# LM339.net
KiCad netlist of a schematic drawn in EAGLE
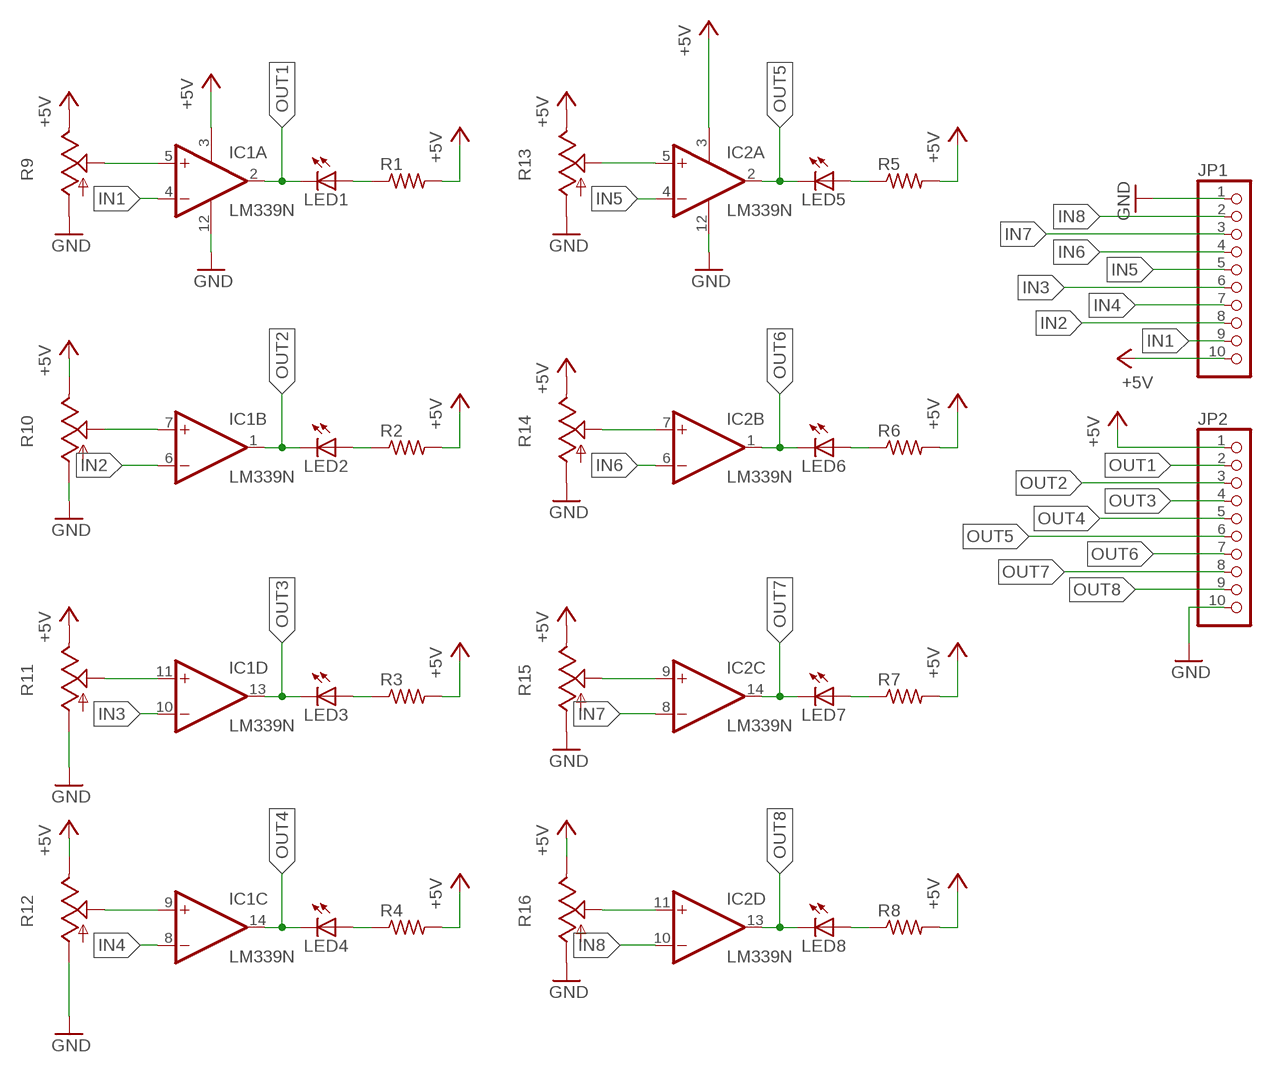
[diagram p0: schematic, sheet 1]

(export (version "E")
  (design (tool "Eeschema 10.0.6"))
  (components
    (comp (ref "IC1")
      (value "LM339N")
      (footprint "eagle-import:DIL14")
      (libsource (lib "eagle-import") (part "LM339N"))
    )
    (comp (ref "IC2")
      (value "LM339N")
      (footprint "eagle-import:DIL14")
      (libsource (lib "eagle-import") (part "LM339N"))
    )
    (comp (ref "JP1")
      (value "PINHD-1X10")
      (footprint "eagle-import:1X10")
      (libsource (lib "eagle-import") (part "PINHD-1X10"))
    )
    (comp (ref "JP2")
      (value "PINHD-1X10")
      (footprint "eagle-import:1X10")
      (libsource (lib "eagle-import") (part "PINHD-1X10"))
    )
    (comp (ref "LED1")
      (value "LED5MM")
      (footprint "eagle-import:LED5MM")
      (libsource (lib "eagle-import") (part "LED5MM"))
    )
    (comp (ref "LED2")
      (value "LED5MM")
      (footprint "eagle-import:LED5MM")
      (libsource (lib "eagle-import") (part "LED5MM"))
    )
    (comp (ref "LED3")
      (value "LED5MM")
      (footprint "eagle-import:LED5MM")
      (libsource (lib "eagle-import") (part "LED5MM"))
    )
    (comp (ref "LED4")
      (value "LED5MM")
      (footprint "eagle-import:LED5MM")
      (libsource (lib "eagle-import") (part "LED5MM"))
    )
    (comp (ref "LED5")
      (value "LED5MM")
      (footprint "eagle-import:LED5MM")
      (libsource (lib "eagle-import") (part "LED5MM"))
    )
    (comp (ref "LED6")
      (value "LED5MM")
      (footprint "eagle-import:LED5MM")
      (libsource (lib "eagle-import") (part "LED5MM"))
    )
    (comp (ref "LED7")
      (value "LED5MM")
      (footprint "eagle-import:LED5MM")
      (libsource (lib "eagle-import") (part "LED5MM"))
    )
    (comp (ref "LED8")
      (value "LED5MM")
      (footprint "eagle-import:LED5MM")
      (libsource (lib "eagle-import") (part "LED5MM"))
    )
    (comp (ref "R1")
      (value "R-US_0204/7")
      (footprint "eagle-import:0204_7")
      (libsource (lib "eagle-import") (part "R-US_0204/7"))
    )
    (comp (ref "R2")
      (value "R-US_0204/7")
      (footprint "eagle-import:0204_7")
      (libsource (lib "eagle-import") (part "R-US_0204/7"))
    )
    (comp (ref "R3")
      (value "R-US_0204/7")
      (footprint "eagle-import:0204_7")
      (libsource (lib "eagle-import") (part "R-US_0204/7"))
    )
    (comp (ref "R4")
      (value "R-US_0204/7")
      (footprint "eagle-import:0204_7")
      (libsource (lib "eagle-import") (part "R-US_0204/7"))
    )
    (comp (ref "R5")
      (value "R-US_0204/7")
      (footprint "eagle-import:0204_7")
      (libsource (lib "eagle-import") (part "R-US_0204/7"))
    )
    (comp (ref "R6")
      (value "R-US_0204/7")
      (footprint "eagle-import:0204_7")
      (libsource (lib "eagle-import") (part "R-US_0204/7"))
    )
    (comp (ref "R7")
      (value "R-US_0204/7")
      (footprint "eagle-import:0204_7")
      (libsource (lib "eagle-import") (part "R-US_0204/7"))
    )
    (comp (ref "R8")
      (value "R-US_0204/7")
      (footprint "eagle-import:0204_7")
      (libsource (lib "eagle-import") (part "R-US_0204/7"))
    )
    (comp (ref "R9")
      (value "TRIM_US-B25P")
      (footprint "eagle-import:B25P")
      (libsource (lib "eagle-import") (part "TRIM_US-B25P"))
    )
    (comp (ref "R10")
      (value "TRIM_US-B25P")
      (footprint "eagle-import:B25P")
      (libsource (lib "eagle-import") (part "TRIM_US-B25P"))
    )
    (comp (ref "R11")
      (value "TRIM_US-B25P")
      (footprint "eagle-import:B25P")
      (libsource (lib "eagle-import") (part "TRIM_US-B25P"))
    )
    (comp (ref "R12")
      (value "TRIM_US-B25P")
      (footprint "eagle-import:B25P")
      (libsource (lib "eagle-import") (part "TRIM_US-B25P"))
    )
    (comp (ref "R13")
      (value "TRIM_US-B25P")
      (footprint "eagle-import:B25P")
      (libsource (lib "eagle-import") (part "TRIM_US-B25P"))
    )
    (comp (ref "R14")
      (value "TRIM_US-B25P")
      (footprint "eagle-import:B25P")
      (libsource (lib "eagle-import") (part "TRIM_US-B25P"))
    )
    (comp (ref "R15")
      (value "TRIM_US-B25P")
      (footprint "eagle-import:B25P")
      (libsource (lib "eagle-import") (part "TRIM_US-B25P"))
    )
    (comp (ref "R16")
      (value "TRIM_US-B25P")
      (footprint "eagle-import:B25P")
      (libsource (lib "eagle-import") (part "TRIM_US-B25P"))
    )
  )
  (nets
    (net (code "1") (name "+5V") (class "Default")
      (node (ref "IC1") (pin "3") (pinfunction "V+_3") (pintype "power_in"))
      (node (ref "IC2") (pin "3") (pinfunction "V+_3") (pintype "power_in"))
      (node (ref "JP1") (pin "10") (pinfunction "10_10") (pintype "passive"))
      (node (ref "JP2") (pin "1") (pinfunction "1_1") (pintype "passive"))
      (node (ref "R1") (pin "2") (pinfunction "2_2") (pintype "passive"))
      (node (ref "R10") (pin "E") (pinfunction "E_E") (pintype "passive"))
      (node (ref "R11") (pin "E") (pinfunction "E_E") (pintype "passive"))
      (node (ref "R12") (pin "E") (pinfunction "E_E") (pintype "passive"))
      (node (ref "R13") (pin "E") (pinfunction "E_E") (pintype "passive"))
      (node (ref "R14") (pin "E") (pinfunction "E_E") (pintype "passive"))
      (node (ref "R15") (pin "E") (pinfunction "E_E") (pintype "passive"))
      (node (ref "R16") (pin "E") (pinfunction "E_E") (pintype "passive"))
      (node (ref "R2") (pin "2") (pinfunction "2_2") (pintype "passive"))
      (node (ref "R3") (pin "2") (pinfunction "2_2") (pintype "passive"))
      (node (ref "R4") (pin "2") (pinfunction "2_2") (pintype "passive"))
      (node (ref "R5") (pin "2") (pinfunction "2_2") (pintype "passive"))
      (node (ref "R6") (pin "2") (pinfunction "2_2") (pintype "passive"))
      (node (ref "R7") (pin "2") (pinfunction "2_2") (pintype "passive"))
      (node (ref "R8") (pin "2") (pinfunction "2_2") (pintype "passive"))
      (node (ref "R9") (pin "E") (pinfunction "E_E") (pintype "passive"))
    )
    (net (code "2") (name "GND") (class "Default")
      (node (ref "IC1") (pin "12") (pinfunction "GND_12") (pintype "power_in"))
      (node (ref "IC2") (pin "12") (pinfunction "GND_12") (pintype "power_in"))
      (node (ref "JP1") (pin "1") (pinfunction "1_1") (pintype "passive"))
      (node (ref "JP2") (pin "10") (pinfunction "10_10") (pintype "passive"))
      (node (ref "R10") (pin "A") (pinfunction "A_A") (pintype "passive"))
      (node (ref "R11") (pin "A") (pinfunction "A_A") (pintype "passive"))
      (node (ref "R12") (pin "A") (pinfunction "A_A") (pintype "passive"))
      (node (ref "R13") (pin "A") (pinfunction "A_A") (pintype "passive"))
      (node (ref "R14") (pin "A") (pinfunction "A_A") (pintype "passive"))
      (node (ref "R15") (pin "A") (pinfunction "A_A") (pintype "passive"))
      (node (ref "R16") (pin "A") (pinfunction "A_A") (pintype "passive"))
      (node (ref "R9") (pin "A") (pinfunction "A_A") (pintype "passive"))
    )
    (net (code "3") (name "IN1") (class "Default")
      (node (ref "IC1") (pin "4") (pinfunction "-IN_4") (pintype "input"))
      (node (ref "JP1") (pin "9") (pinfunction "9_9") (pintype "passive"))
    )
    (net (code "4") (name "IN2") (class "Default")
      (node (ref "IC1") (pin "6") (pinfunction "-IN_6") (pintype "input"))
      (node (ref "JP1") (pin "8") (pinfunction "8_8") (pintype "passive"))
    )
    (net (code "5") (name "IN3") (class "Default")
      (node (ref "IC1") (pin "10") (pinfunction "-IN_10") (pintype "input"))
      (node (ref "JP1") (pin "6") (pinfunction "6_6") (pintype "passive"))
    )
    (net (code "6") (name "IN4") (class "Default")
      (node (ref "IC1") (pin "8") (pinfunction "-IN_8") (pintype "input"))
      (node (ref "JP1") (pin "7") (pinfunction "7_7") (pintype "passive"))
    )
    (net (code "7") (name "IN5") (class "Default")
      (node (ref "IC2") (pin "4") (pinfunction "-IN_4") (pintype "input"))
      (node (ref "JP1") (pin "5") (pinfunction "5_5") (pintype "passive"))
    )
    (net (code "8") (name "IN6") (class "Default")
      (node (ref "IC2") (pin "6") (pinfunction "-IN_6") (pintype "input"))
      (node (ref "JP1") (pin "4") (pinfunction "4_4") (pintype "passive"))
    )
    (net (code "9") (name "IN7") (class "Default")
      (node (ref "IC2") (pin "8") (pinfunction "-IN_8") (pintype "input"))
      (node (ref "JP1") (pin "3") (pinfunction "3_3") (pintype "passive"))
    )
    (net (code "10") (name "IN8") (class "Default")
      (node (ref "IC2") (pin "10") (pinfunction "-IN_10") (pintype "input"))
      (node (ref "JP1") (pin "2") (pinfunction "2_2") (pintype "passive"))
    )
    (net (code "11") (name "Net-(IC1A-+IN)") (class "Default")
      (node (ref "IC1") (pin "5") (pinfunction "+IN_5") (pintype "input"))
      (node (ref "R9") (pin "S") (pinfunction "S_S") (pintype "passive"))
    )
    (net (code "12") (name "Net-(IC1B-+IN)") (class "Default")
      (node (ref "IC1") (pin "7") (pinfunction "+IN_7") (pintype "input"))
      (node (ref "R10") (pin "S") (pinfunction "S_S") (pintype "passive"))
    )
    (net (code "13") (name "Net-(IC1C-+IN)") (class "Default")
      (node (ref "IC1") (pin "9") (pinfunction "+IN_9") (pintype "input"))
      (node (ref "R12") (pin "S") (pinfunction "S_S") (pintype "passive"))
    )
    (net (code "14") (name "Net-(IC1D-+IN)") (class "Default")
      (node (ref "IC1") (pin "11") (pinfunction "+IN_11") (pintype "input"))
      (node (ref "R11") (pin "S") (pinfunction "S_S") (pintype "passive"))
    )
    (net (code "15") (name "Net-(IC2A-+IN)") (class "Default")
      (node (ref "IC2") (pin "5") (pinfunction "+IN_5") (pintype "input"))
      (node (ref "R13") (pin "S") (pinfunction "S_S") (pintype "passive"))
    )
    (net (code "16") (name "Net-(IC2B-+IN)") (class "Default")
      (node (ref "IC2") (pin "7") (pinfunction "+IN_7") (pintype "input"))
      (node (ref "R14") (pin "S") (pinfunction "S_S") (pintype "passive"))
    )
    (net (code "17") (name "Net-(IC2C-+IN)") (class "Default")
      (node (ref "IC2") (pin "9") (pinfunction "+IN_9") (pintype "input"))
      (node (ref "R15") (pin "S") (pinfunction "S_S") (pintype "passive"))
    )
    (net (code "18") (name "Net-(IC2D-+IN)") (class "Default")
      (node (ref "IC2") (pin "11") (pinfunction "+IN_11") (pintype "input"))
      (node (ref "R16") (pin "S") (pinfunction "S_S") (pintype "passive"))
    )
    (net (code "19") (name "Net-(LED1-PadA)") (class "Default")
      (node (ref "LED1") (pin "A") (pinfunction "A_A") (pintype "passive"))
      (node (ref "R1") (pin "1") (pinfunction "1_1") (pintype "passive"))
    )
    (net (code "20") (name "Net-(LED2-PadA)") (class "Default")
      (node (ref "LED2") (pin "A") (pinfunction "A_A") (pintype "passive"))
      (node (ref "R2") (pin "1") (pinfunction "1_1") (pintype "passive"))
    )
    (net (code "21") (name "Net-(LED3-PadA)") (class "Default")
      (node (ref "LED3") (pin "A") (pinfunction "A_A") (pintype "passive"))
      (node (ref "R3") (pin "1") (pinfunction "1_1") (pintype "passive"))
    )
    (net (code "22") (name "Net-(LED4-PadA)") (class "Default")
      (node (ref "LED4") (pin "A") (pinfunction "A_A") (pintype "passive"))
      (node (ref "R4") (pin "1") (pinfunction "1_1") (pintype "passive"))
    )
    (net (code "23") (name "Net-(LED5-PadA)") (class "Default")
      (node (ref "LED5") (pin "A") (pinfunction "A_A") (pintype "passive"))
      (node (ref "R5") (pin "1") (pinfunction "1_1") (pintype "passive"))
    )
    (net (code "24") (name "Net-(LED6-PadA)") (class "Default")
      (node (ref "LED6") (pin "A") (pinfunction "A_A") (pintype "passive"))
      (node (ref "R6") (pin "1") (pinfunction "1_1") (pintype "passive"))
    )
    (net (code "25") (name "Net-(LED7-PadA)") (class "Default")
      (node (ref "LED7") (pin "A") (pinfunction "A_A") (pintype "passive"))
      (node (ref "R7") (pin "1") (pinfunction "1_1") (pintype "passive"))
    )
    (net (code "26") (name "Net-(LED8-PadA)") (class "Default")
      (node (ref "LED8") (pin "A") (pinfunction "A_A") (pintype "passive"))
      (node (ref "R8") (pin "1") (pinfunction "1_1") (pintype "passive"))
    )
    (net (code "27") (name "OUT1") (class "Default")
      (node (ref "IC1") (pin "2") (pinfunction "OUT_2") (pintype "open_collector"))
      (node (ref "JP2") (pin "2") (pinfunction "2_2") (pintype "passive"))
      (node (ref "LED1") (pin "K") (pinfunction "C_K") (pintype "passive"))
    )
    (net (code "28") (name "OUT2") (class "Default")
      (node (ref "IC1") (pin "1") (pinfunction "OUT_1") (pintype "open_collector"))
      (node (ref "JP2") (pin "3") (pinfunction "3_3") (pintype "passive"))
      (node (ref "LED2") (pin "K") (pinfunction "C_K") (pintype "passive"))
    )
    (net (code "29") (name "OUT3") (class "Default")
      (node (ref "IC1") (pin "13") (pinfunction "OUT_13") (pintype "open_collector"))
      (node (ref "JP2") (pin "4") (pinfunction "4_4") (pintype "passive"))
      (node (ref "LED3") (pin "K") (pinfunction "C_K") (pintype "passive"))
    )
    (net (code "30") (name "OUT4") (class "Default")
      (node (ref "IC1") (pin "14") (pinfunction "OUT_14") (pintype "open_collector"))
      (node (ref "JP2") (pin "5") (pinfunction "5_5") (pintype "passive"))
      (node (ref "LED4") (pin "K") (pinfunction "C_K") (pintype "passive"))
    )
    (net (code "31") (name "OUT5") (class "Default")
      (node (ref "IC2") (pin "2") (pinfunction "OUT_2") (pintype "open_collector"))
      (node (ref "JP2") (pin "6") (pinfunction "6_6") (pintype "passive"))
      (node (ref "LED5") (pin "K") (pinfunction "C_K") (pintype "passive"))
    )
    (net (code "32") (name "OUT6") (class "Default")
      (node (ref "IC2") (pin "1") (pinfunction "OUT_1") (pintype "open_collector"))
      (node (ref "JP2") (pin "7") (pinfunction "7_7") (pintype "passive"))
      (node (ref "LED6") (pin "K") (pinfunction "C_K") (pintype "passive"))
    )
    (net (code "33") (name "OUT7") (class "Default")
      (node (ref "IC2") (pin "14") (pinfunction "OUT_14") (pintype "open_collector"))
      (node (ref "JP2") (pin "8") (pinfunction "8_8") (pintype "passive"))
      (node (ref "LED7") (pin "K") (pinfunction "C_K") (pintype "passive"))
    )
    (net (code "34") (name "OUT8") (class "Default")
      (node (ref "IC2") (pin "13") (pinfunction "OUT_13") (pintype "open_collector"))
      (node (ref "JP2") (pin "9") (pinfunction "9_9") (pintype "passive"))
      (node (ref "LED8") (pin "K") (pinfunction "C_K") (pintype "passive"))
    )
  )
)
